# Mag_Encoder_TLE5501.net
KiCad netlist of a schematic drawn in Altium Designer
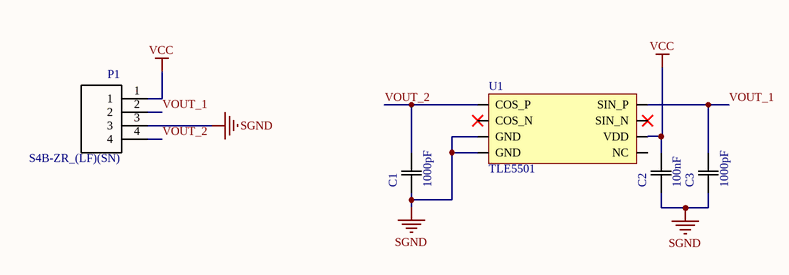
[diagram p0: Mag_Encoder_TLE5501.SchDoc]

(export (version "E")
  (design (tool "Eeschema 10.0.6"))
  (components
    (comp (ref "C1")
      (value "1000pF")
      (footprint "0805")
      (description "CAP CER 1000PF 50V X7R 0805")
      (fields (field (name "MP") "C0805C102K5RACTU") (field (name "MF") "Kemet"))
      (libsource (lib "AltiumLibraries") (part "CAP 1000pF 0805"))
    )
    (comp (ref "C2")
      (value "100nF")
      (footprint "0805")
      (description "CAP CER 0.1UF 50V X7R 0805")
      (fields (field (name "MP") "CC0805KRX7R9BB104") (field (name "MF") "Yageo"))
      (libsource (lib "AltiumLibraries") (part "CAP 100nF 0805"))
    )
    (comp (ref "C3")
      (value "1000pF")
      (footprint "0805")
      (description "CAP CER 1000PF 50V X7R 0805")
      (fields (field (name "MP") "C0805C102K5RACTU") (field (name "MF") "Kemet"))
      (libsource (lib "AltiumLibraries") (part "CAP 1000pF 0805"))
    )
    (comp (ref "P1")
      (value "S4B-ZR_(LF)(SN)")
      (footprint "*JST_S4B-ZR(LF)(SN)")
      (description "Conn Shrouded Header HDR 4 POS 1.5mm Solder RA Thru-Hole Box")
      (fields (field (name "MP") "S4B-ZR _LF__SN_") (field (name "MF") "JST Sales"))
      (libsource (lib "AltiumLibraries") (part "S4B-ZR_(LF)(SN)"))
    )
    (comp (ref "U1")
      (value "TLE5501")
      (footprint "8-SOIC TLE5XXX ENC")
      (description "TMR 360deg Magnetic Encoder")
      (fields
        (field (name "MANUFACTURER") "Infineon Technologies")
        (field (name "MANUFACTURER PART NUMBER") "TLE5501E0001XUMA1")
      )
      (libsource (lib "AltiumLibraries") (part "TLE5501"))
    )
  )
  (nets
    (net (code "1") (name "/VOUT_1") (class "Default")
      (node (ref "C3") (pin "2") (pinfunction "C2_2") (pintype "passive"))
      (node (ref "P1") (pin "2") (pinfunction "2_2") (pintype "passive"))
      (node (ref "U1") (pin "8") (pinfunction "SIN_P_8") (pintype "passive"))
    )
    (net (code "2") (name "/VOUT_2") (class "Default")
      (node (ref "C1") (pin "2") (pinfunction "C2_2") (pintype "passive"))
      (node (ref "P1") (pin "4") (pinfunction "4_4") (pintype "passive"))
      (node (ref "U1") (pin "1") (pinfunction "COS_P_1") (pintype "passive"))
    )
    (net (code "3") (name "SGND") (class "Default")
      (node (ref "C1") (pin "1") (pinfunction "C1_1") (pintype "passive"))
      (node (ref "C2") (pin "1") (pinfunction "C1_1") (pintype "passive"))
      (node (ref "C3") (pin "1") (pinfunction "C1_1") (pintype "passive"))
      (node (ref "P1") (pin "3") (pinfunction "3_3") (pintype "passive"))
      (node (ref "U1") (pin "3") (pinfunction "GND_3") (pintype "passive"))
      (node (ref "U1") (pin "4") (pinfunction "GND_4") (pintype "passive"))
    )
    (net (code "4") (name "VCC") (class "Default")
      (node (ref "C2") (pin "2") (pinfunction "C2_2") (pintype "passive"))
      (node (ref "P1") (pin "1") (pinfunction "1_1") (pintype "passive"))
      (node (ref "U1") (pin "6") (pinfunction "VDD_6") (pintype "passive"))
    )
    (net (code "5") (name "unconnected-(U1-COS_N-Pad2)") (class "Default")
      (node (ref "U1") (pin "2") (pinfunction "COS_N_2") (pintype "passive+no_connect"))
    )
    (net (code "6") (name "unconnected-(U1-NC-Pad5)") (class "Default")
      (node (ref "U1") (pin "5") (pinfunction "NC_5") (pintype "passive"))
    )
    (net (code "7") (name "unconnected-(U1-SIN_N-Pad7)") (class "Default")
      (node (ref "U1") (pin "7") (pinfunction "SIN_N_7") (pintype "passive+no_connect"))
    )
  )
)
